# GH_Terra_one_side_corr.net
KiCad netlist of a schematic drawn in EAGLE
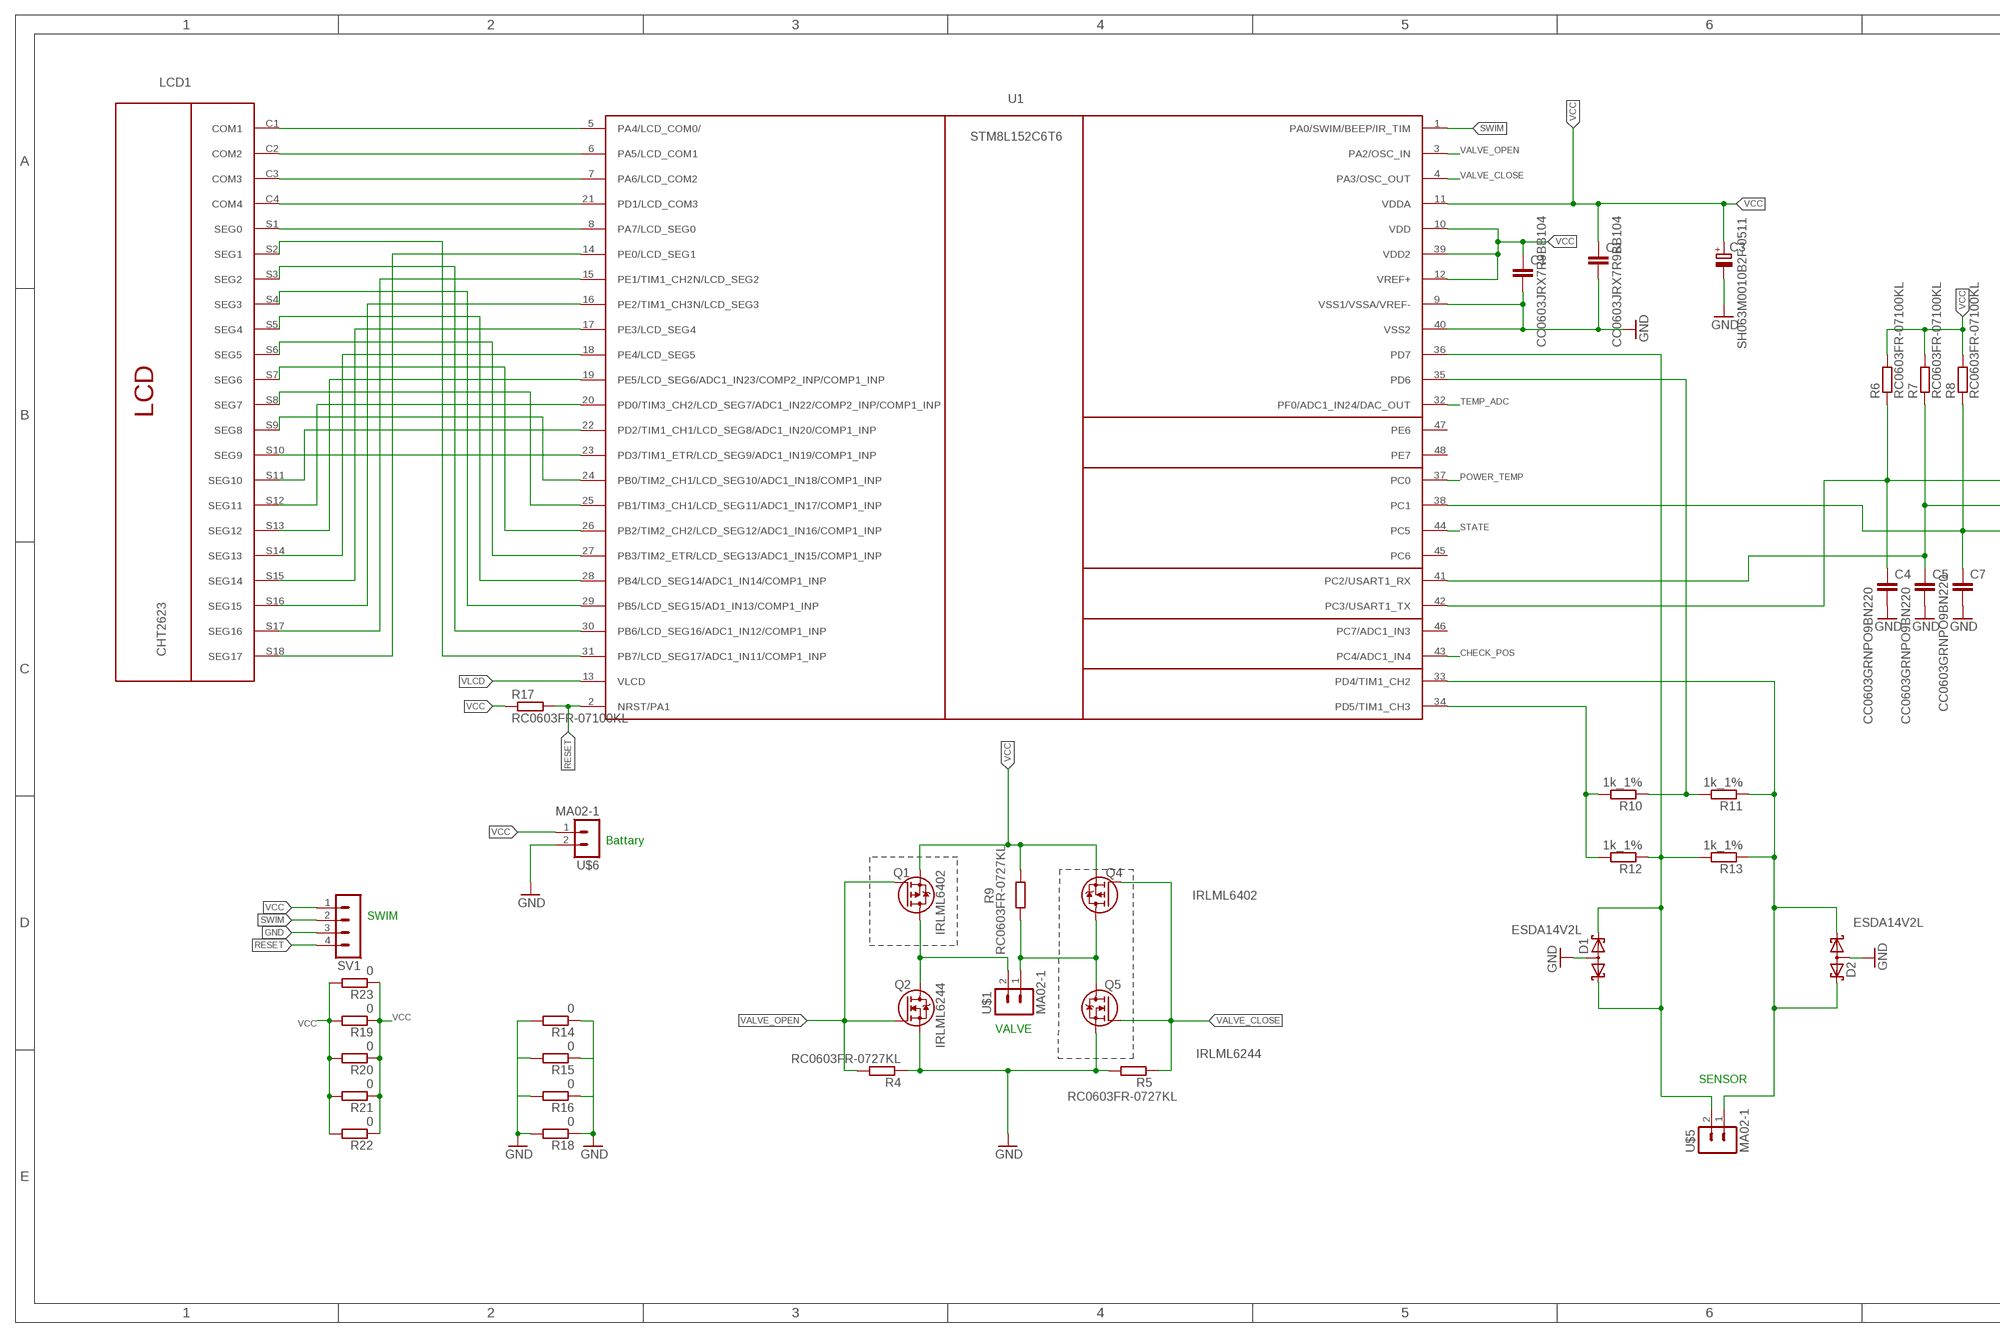
[diagram p0: schematic, sheet 1, part 1 of 2]
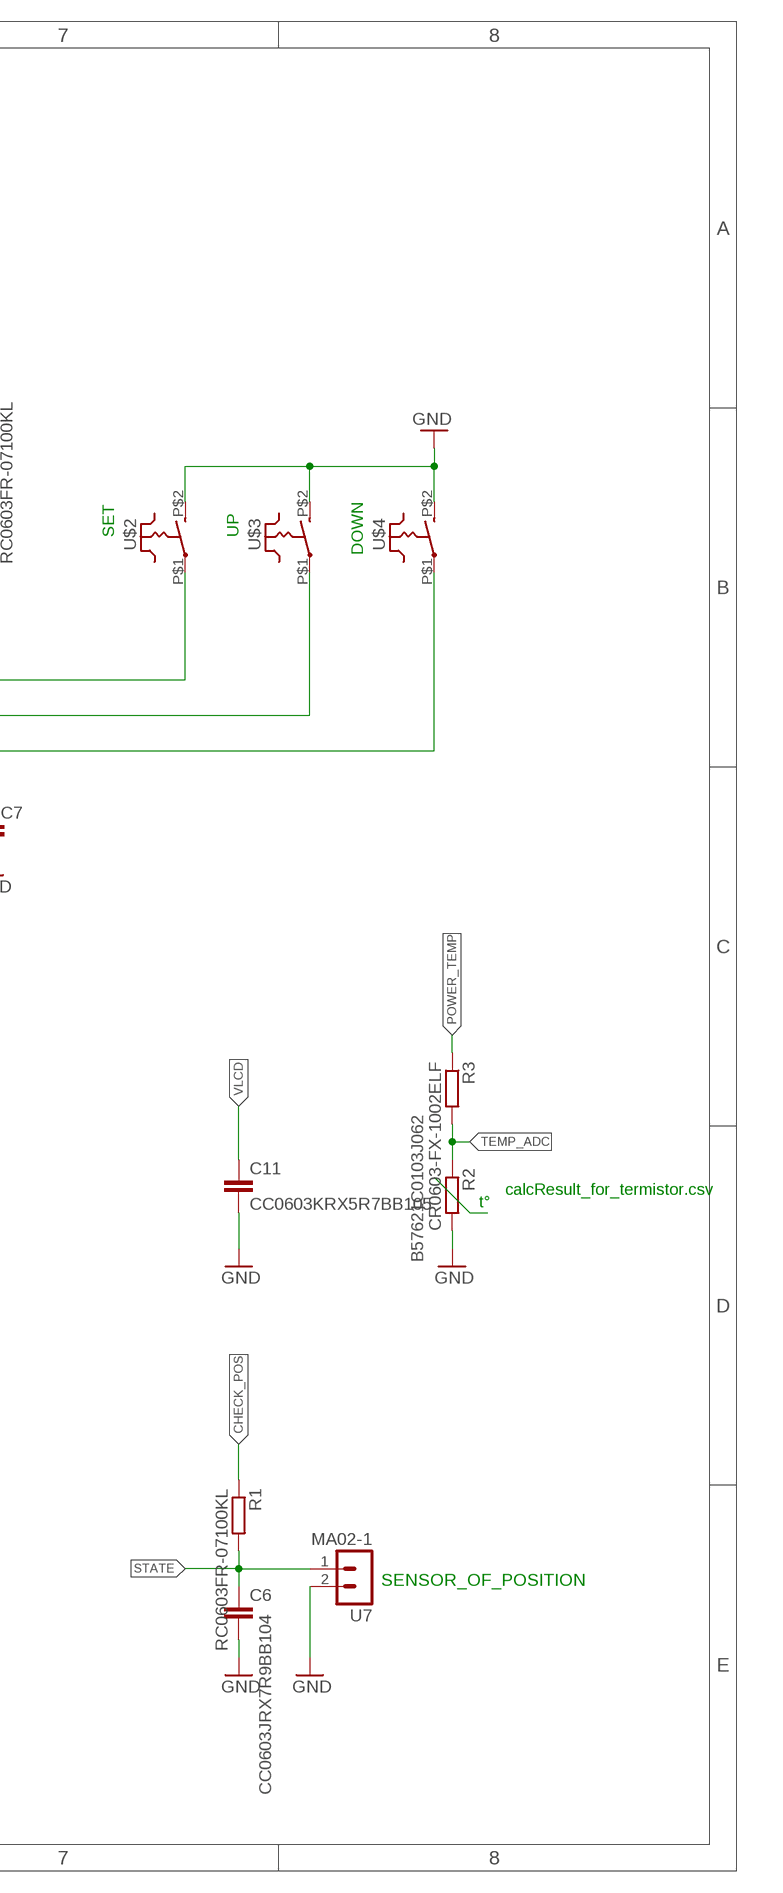
[diagram p1: schematic, sheet 1, part 2 of 2]

(export (version "E")
  (design (tool "Eeschema 10.0.6"))
  (components
    (comp (ref "C1")
      (value "CC0603JRX7R9BB104")
      (footprint "eagle-import:C0603_IPC")
      (libsource (lib "eagle-import") (part "C-EUC0603"))
    )
    (comp (ref "C2")
      (value "CC0603JRX7R9BB104")
      (footprint "eagle-import:C0603_IPC")
      (libsource (lib "eagle-import") (part "C-EUC0603"))
    )
    (comp (ref "C3")
      (value "SH063M0010B2F-0511")
      (footprint "eagle-import:SANYO-OSCON_C6")
      (libsource (lib "eagle-import") (part "CPOL-EUSANYO_C6"))
    )
    (comp (ref "C4")
      (value "CC0603GRNPO9BN220")
      (footprint "eagle-import:C0603_IPC")
      (libsource (lib "eagle-import") (part "C-EUC0603"))
    )
    (comp (ref "C5")
      (value "CC0603GRNPO9BN220")
      (footprint "eagle-import:C0603_IPC")
      (libsource (lib "eagle-import") (part "C-EUC0603"))
    )
    (comp (ref "C6")
      (value "CC0603JRX7R9BB104")
      (footprint "eagle-import:C0603_IPC")
      (libsource (lib "eagle-import") (part "C-EUC0603"))
    )
    (comp (ref "C7")
      (value "CC0603GRNPO9BN220")
      (footprint "eagle-import:C0603_IPC")
      (libsource (lib "eagle-import") (part "C-EUC0603"))
    )
    (comp (ref "C11")
      (value "CC0603KRX5R7BB105")
      (footprint "eagle-import:C0603_IPC")
      (libsource (lib "eagle-import") (part "C-EUC0603"))
    )
    (comp (ref "D1")
      (value "ESDA14V2L")
      (footprint "eagle-import:SOT23")
      (libsource (lib "eagle-import") (part "BAS40-06"))
    )
    (comp (ref "D2")
      (value "ESDA14V2L")
      (footprint "eagle-import:SOT23")
      (libsource (lib "eagle-import") (part "BAS40-06"))
    )
    (comp (ref "LCD1")
      (value "CHT2623")
      (footprint "eagle-import:CHT2623")
      (libsource (lib "eagle-import") (part "CHT2623"))
    )
    (comp (ref "Q1")
      (value "IRLML6402")
      (footprint "eagle-import:SOT23")
      (libsource (lib "eagle-import") (part "PFET-SOT23"))
    )
    (comp (ref "Q2")
      (value "IRLML6244")
      (footprint "eagle-import:SOT23")
      (libsource (lib "eagle-import") (part "NFET-SOT23"))
    )
    (comp (ref "Q4")
      (value "IRLML6402")
      (footprint "eagle-import:SOT23")
      (libsource (lib "eagle-import") (part "PFET-SOT23"))
    )
    (comp (ref "Q5")
      (value "IRLML6244")
      (footprint "eagle-import:SOT23")
      (libsource (lib "eagle-import") (part "NFET-SOT23"))
    )
    (comp (ref "R1")
      (value "RC0603FR-07100KL")
      (footprint "eagle-import:R0603_IPC")
      (libsource (lib "eagle-import") (part "R-EU_R0603"))
    )
    (comp (ref "R2")
      (value "B57621C0103J062")
      (footprint "eagle-import:R1206")
      (libsource (lib "eagle-import") (part "R-EU_R1206"))
    )
    (comp (ref "R3")
      (value "CR0603-FX-1002ELF")
      (footprint "eagle-import:R0603_IPC")
      (libsource (lib "eagle-import") (part "R-EU_R0603"))
    )
    (comp (ref "R4")
      (value "RC0603FR-0727KL")
      (footprint "eagle-import:R0603_IPC")
      (libsource (lib "eagle-import") (part "R-EU_R0603"))
    )
    (comp (ref "R5")
      (value "RC0603FR-0727KL")
      (footprint "eagle-import:R0603_IPC")
      (libsource (lib "eagle-import") (part "R-EU_R0603"))
    )
    (comp (ref "R6")
      (value "RC0603FR-07100KL")
      (footprint "eagle-import:R0603_IPC")
      (libsource (lib "eagle-import") (part "R-EU_R0603"))
    )
    (comp (ref "R7")
      (value "RC0603FR-07100KL")
      (footprint "eagle-import:R0603_IPC")
      (libsource (lib "eagle-import") (part "R-EU_R0603"))
    )
    (comp (ref "R8")
      (value "RC0603FR-07100KL")
      (footprint "eagle-import:R0603_IPC")
      (libsource (lib "eagle-import") (part "R-EU_R0603"))
    )
    (comp (ref "R9")
      (value "RC0603FR-0727KL")
      (footprint "eagle-import:R0603_IPC")
      (libsource (lib "eagle-import") (part "R-EU_R0603"))
    )
    (comp (ref "R10")
      (value "1k_1%")
      (footprint "eagle-import:R0603_IPC")
      (libsource (lib "eagle-import") (part "R-EU_R0603"))
    )
    (comp (ref "R11")
      (value "1k_1%")
      (footprint "eagle-import:R0603_IPC")
      (libsource (lib "eagle-import") (part "R-EU_R0603"))
    )
    (comp (ref "R12")
      (value "1k_1%")
      (footprint "eagle-import:R0603_IPC")
      (libsource (lib "eagle-import") (part "R-EU_R0603"))
    )
    (comp (ref "R13")
      (value "1k_1%")
      (footprint "eagle-import:R0603_IPC")
      (libsource (lib "eagle-import") (part "R-EU_R0603"))
    )
    (comp (ref "R14")
      (value "0")
      (footprint "eagle-import:R0603_IPC")
      (libsource (lib "eagle-import") (part "R-EU_R0603"))
    )
    (comp (ref "R15")
      (value "0")
      (footprint "eagle-import:R0603_IPC")
      (libsource (lib "eagle-import") (part "R-EU_R0603"))
    )
    (comp (ref "R16")
      (value "0")
      (footprint "eagle-import:R0603_IPC")
      (libsource (lib "eagle-import") (part "R-EU_R0603"))
    )
    (comp (ref "R17")
      (value "RC0603FR-07100KL")
      (footprint "eagle-import:R0603_IPC")
      (libsource (lib "eagle-import") (part "R-EU_R0603"))
    )
    (comp (ref "R18")
      (value "0")
      (footprint "eagle-import:R0603_IPC")
      (libsource (lib "eagle-import") (part "R-EU_R0603"))
    )
    (comp (ref "R19")
      (value "0")
      (footprint "eagle-import:R0603_IPC")
      (libsource (lib "eagle-import") (part "R-EU_R0603"))
    )
    (comp (ref "R20")
      (value "0")
      (footprint "eagle-import:R0603_IPC")
      (libsource (lib "eagle-import") (part "R-EU_R0603"))
    )
    (comp (ref "R21")
      (value "0")
      (footprint "eagle-import:R0603_IPC")
      (libsource (lib "eagle-import") (part "R-EU_R0603"))
    )
    (comp (ref "R22")
      (value "0")
      (footprint "eagle-import:R0603_IPC")
      (libsource (lib "eagle-import") (part "R-EU_R0603"))
    )
    (comp (ref "R23")
      (value "0")
      (footprint "eagle-import:R0603_IPC")
      (libsource (lib "eagle-import") (part "R-EU_R0603"))
    )
    (comp (ref "SV1")
      (value "MA04-1")
      (footprint "eagle-import:MA04-1")
      (libsource (lib "eagle-import") (part "MA04-1"))
    )
    (comp (ref "U$1")
      (value "MA02-1")
      (footprint "eagle-import:MA02-1")
      (libsource (lib "eagle-import") (part "MA02-1"))
    )
    (comp (ref "U$2")
      (value "RK_4X3")
      (footprint "eagle-import:RK_3X4")
      (libsource (lib "eagle-import") (part "RK_4X3"))
    )
    (comp (ref "U$3")
      (value "RK_4X3")
      (footprint "eagle-import:RK_3X4")
      (libsource (lib "eagle-import") (part "RK_4X3"))
    )
    (comp (ref "U$4")
      (value "RK_4X3")
      (footprint "eagle-import:RK_3X4")
      (libsource (lib "eagle-import") (part "RK_4X3"))
    )
    (comp (ref "U$5")
      (value "MA02-1")
      (footprint "eagle-import:MA02-1")
      (libsource (lib "eagle-import") (part "MA02-1"))
    )
    (comp (ref "U$6")
      (value "MA02-1")
      (footprint "eagle-import:MA02-1")
      (libsource (lib "eagle-import") (part "MA02-1"))
    )
    (comp (ref "U1")
      (value "STM8L152C6T6")
      (footprint "eagle-import:LQFP48")
      (libsource (lib "eagle-import") (part "STM8L152C6"))
    )
    (comp (ref "U7")
      (value "MA02-1")
      (footprint "eagle-import:MA02-1")
      (libsource (lib "eagle-import") (part "MA02-1"))
    )
  )
  (nets
    (net (code "1") (name "CHECK_POS") (class "Default")
      (node (ref "R1") (pin "1") (pinfunction "1_1") (pintype "passive"))
      (node (ref "U1") (pin "43") (pinfunction "PC4/ADC1_IN4_43") (pintype "bidirectional"))
    )
    (net (code "2") (name "GND") (class "Default")
      (node (ref "C1") (pin "2") (pinfunction "2_2") (pintype "passive"))
      (node (ref "C11") (pin "2") (pinfunction "2_2") (pintype "passive"))
      (node (ref "C2") (pin "2") (pinfunction "2_2") (pintype "passive"))
      (node (ref "C3") (pin "-") (pinfunction "-_-") (pintype "passive"))
      (node (ref "C4") (pin "2") (pinfunction "2_2") (pintype "passive"))
      (node (ref "C5") (pin "2") (pinfunction "2_2") (pintype "passive"))
      (node (ref "C6") (pin "2") (pinfunction "2_2") (pintype "passive"))
      (node (ref "C7") (pin "2") (pinfunction "2_2") (pintype "passive"))
      (node (ref "D1") (pin "3") (pinfunction "AA_3") (pintype "passive"))
      (node (ref "D2") (pin "3") (pinfunction "AA_3") (pintype "passive"))
      (node (ref "Q2") (pin "2") (pinfunction "S_2") (pintype "passive"))
      (node (ref "Q5") (pin "2") (pinfunction "S_2") (pintype "passive"))
      (node (ref "R14") (pin "1") (pinfunction "1_1") (pintype "passive"))
      (node (ref "R14") (pin "2") (pinfunction "2_2") (pintype "passive"))
      (node (ref "R15") (pin "1") (pinfunction "1_1") (pintype "passive"))
      (node (ref "R15") (pin "2") (pinfunction "2_2") (pintype "passive"))
      (node (ref "R16") (pin "1") (pinfunction "1_1") (pintype "passive"))
      (node (ref "R16") (pin "2") (pinfunction "2_2") (pintype "passive"))
      (node (ref "R18") (pin "1") (pinfunction "1_1") (pintype "passive"))
      (node (ref "R18") (pin "2") (pinfunction "2_2") (pintype "passive"))
      (node (ref "R2") (pin "2") (pinfunction "2_2") (pintype "passive"))
      (node (ref "R4") (pin "1") (pinfunction "1_1") (pintype "passive"))
      (node (ref "R5") (pin "2") (pinfunction "2_2") (pintype "passive"))
      (node (ref "SV1") (pin "3") (pinfunction "3_3") (pintype "passive"))
      (node (ref "U$2") (pin "P$2") (pinfunction "S_P$2") (pintype "passive"))
      (node (ref "U$3") (pin "P$2") (pinfunction "S_P$2") (pintype "passive"))
      (node (ref "U$4") (pin "P$2") (pinfunction "S_P$2") (pintype "passive"))
      (node (ref "U$6") (pin "2") (pinfunction "2_2") (pintype "passive"))
      (node (ref "U1") (pin "40") (pinfunction "VSS2_40") (pintype "bidirectional"))
      (node (ref "U1") (pin "9") (pinfunction "VSS1/VSSA/VREF-_9") (pintype "bidirectional"))
      (node (ref "U7") (pin "2") (pinfunction "2_2") (pintype "passive"))
    )
    (net (code "3") (name "Net-(D1-K1)") (class "Default")
      (node (ref "D1") (pin "1") (pinfunction "K1_1") (pintype "passive"))
      (node (ref "D1") (pin "2") (pinfunction "K2_2") (pintype "passive"))
      (node (ref "R12") (pin "1") (pinfunction "1_1") (pintype "passive"))
      (node (ref "R13") (pin "2") (pinfunction "2_2") (pintype "passive"))
      (node (ref "U$5") (pin "2") (pinfunction "2_2") (pintype "passive"))
      (node (ref "U1") (pin "36") (pinfunction "PD7_36") (pintype "bidirectional"))
    )
    (net (code "4") (name "Net-(D2-K1)") (class "Default")
      (node (ref "D2") (pin "1") (pinfunction "K1_1") (pintype "passive"))
      (node (ref "D2") (pin "2") (pinfunction "K2_2") (pintype "passive"))
      (node (ref "R11") (pin "1") (pinfunction "1_1") (pintype "passive"))
      (node (ref "R13") (pin "1") (pinfunction "1_1") (pintype "passive"))
      (node (ref "U$5") (pin "1") (pinfunction "1_1") (pintype "passive"))
      (node (ref "U1") (pin "33") (pinfunction "PD4/TIM1_CH2_33") (pintype "bidirectional"))
    )
    (net (code "5") (name "Net-(LCD1-COM1)") (class "Default")
      (node (ref "LCD1") (pin "C1") (pinfunction "COM1_C1") (pintype "bidirectional"))
      (node (ref "U1") (pin "5") (pinfunction "PA4/LCD_COM0/_5") (pintype "bidirectional"))
    )
    (net (code "6") (name "Net-(LCD1-COM2)") (class "Default")
      (node (ref "LCD1") (pin "C2") (pinfunction "COM2_C2") (pintype "bidirectional"))
      (node (ref "U1") (pin "6") (pinfunction "PA5/LCD_COM1_6") (pintype "bidirectional"))
    )
    (net (code "7") (name "Net-(LCD1-COM3)") (class "Default")
      (node (ref "LCD1") (pin "C3") (pinfunction "COM3_C3") (pintype "bidirectional"))
      (node (ref "U1") (pin "7") (pinfunction "PA6/LCD_COM2_7") (pintype "bidirectional"))
    )
    (net (code "8") (name "Net-(LCD1-COM4)") (class "Default")
      (node (ref "LCD1") (pin "C4") (pinfunction "COM4_C4") (pintype "bidirectional"))
      (node (ref "U1") (pin "21") (pinfunction "PD1/LCD_COM3_21") (pintype "bidirectional"))
    )
    (net (code "9") (name "Net-(LCD1-SEG0)") (class "Default")
      (node (ref "LCD1") (pin "S1") (pinfunction "SEG0_S1") (pintype "bidirectional"))
      (node (ref "U1") (pin "8") (pinfunction "PA7/LCD_SEG0_8") (pintype "bidirectional"))
    )
    (net (code "10") (name "Net-(LCD1-SEG1)") (class "Default")
      (node (ref "LCD1") (pin "S2") (pinfunction "SEG1_S2") (pintype "bidirectional"))
      (node (ref "U1") (pin "31") (pinfunction "PB7/LCD_SEG17/ADC1_IN11/COMP1_INP_31") (pintype "bidirectional"))
    )
    (net (code "11") (name "Net-(LCD1-SEG2)") (class "Default")
      (node (ref "LCD1") (pin "S3") (pinfunction "SEG2_S3") (pintype "bidirectional"))
      (node (ref "U1") (pin "30") (pinfunction "PB6/LCD_SEG16/ADC1_IN12/COMP1_INP_30") (pintype "bidirectional"))
    )
    (net (code "12") (name "Net-(LCD1-SEG3)") (class "Default")
      (node (ref "LCD1") (pin "S4") (pinfunction "SEG3_S4") (pintype "bidirectional"))
      (node (ref "U1") (pin "29") (pinfunction "PB5/LCD_SEG15/AD1_IN13/COMP1_INP_29") (pintype "bidirectional"))
    )
    (net (code "13") (name "Net-(LCD1-SEG4)") (class "Default")
      (node (ref "LCD1") (pin "S5") (pinfunction "SEG4_S5") (pintype "bidirectional"))
      (node (ref "U1") (pin "28") (pinfunction "PB4/LCD_SEG14/ADC1_IN14/COMP1_INP_28") (pintype "bidirectional"))
    )
    (net (code "14") (name "Net-(LCD1-SEG5)") (class "Default")
      (node (ref "LCD1") (pin "S6") (pinfunction "SEG5_S6") (pintype "bidirectional"))
      (node (ref "U1") (pin "27") (pinfunction "PB3/TIM2_ETR/LCD_SEG13/ADC1_IN15/COMP1_INP_27") (pintype "bidirectional"))
    )
    (net (code "15") (name "Net-(LCD1-SEG6)") (class "Default")
      (node (ref "LCD1") (pin "S7") (pinfunction "SEG6_S7") (pintype "bidirectional"))
      (node (ref "U1") (pin "26") (pinfunction "PB2/TIM2_CH2/LCD_SEG12/ADC1_IN16/COMP1_INP_26") (pintype "bidirectional"))
    )
    (net (code "16") (name "Net-(LCD1-SEG7)") (class "Default")
      (node (ref "LCD1") (pin "S8") (pinfunction "SEG7_S8") (pintype "bidirectional"))
      (node (ref "U1") (pin "25") (pinfunction "PB1/TIM3_CH1/LCD_SEG11/ADC1_IN17/COMP1_INP_25") (pintype "bidirectional"))
    )
    (net (code "17") (name "Net-(LCD1-SEG8)") (class "Default")
      (node (ref "LCD1") (pin "S9") (pinfunction "SEG8_S9") (pintype "bidirectional"))
      (node (ref "U1") (pin "24") (pinfunction "PB0/TIM2_CH1/LCD_SEG10/ADC1_IN18/COMP1_INP_24") (pintype "bidirectional"))
    )
    (net (code "18") (name "Net-(LCD1-SEG9)") (class "Default")
      (node (ref "LCD1") (pin "S10") (pinfunction "SEG9_S10") (pintype "bidirectional"))
      (node (ref "U1") (pin "23") (pinfunction "PD3/TIM1_ETR/LCD_SEG9/ADC1_IN19/COMP1_INP_23") (pintype "bidirectional"))
    )
    (net (code "19") (name "Net-(LCD1-SEG10)") (class "Default")
      (node (ref "LCD1") (pin "S11") (pinfunction "SEG10_S11") (pintype "bidirectional"))
      (node (ref "U1") (pin "22") (pinfunction "PD2/TIM1_CH1/LCD_SEG8/ADC1_IN20/COMP1_INP_22") (pintype "bidirectional"))
    )
    (net (code "20") (name "Net-(LCD1-SEG11)") (class "Default")
      (node (ref "LCD1") (pin "S12") (pinfunction "SEG11_S12") (pintype "bidirectional"))
      (node (ref "U1") (pin "20") (pinfunction "PD0/TIM3_CH2/LCD_SEG7/ADC1_IN22/COMP2_INP/COMP1_INP_20") (pintype "bidirectional"))
    )
    (net (code "21") (name "Net-(LCD1-SEG12)") (class "Default")
      (node (ref "LCD1") (pin "S13") (pinfunction "SEG12_S13") (pintype "bidirectional"))
      (node (ref "U1") (pin "19") (pinfunction "PE5/LCD_SEG6/ADC1_IN23/COMP2_INP/COMP1_INP_19") (pintype "bidirectional"))
    )
    (net (code "22") (name "Net-(LCD1-SEG13)") (class "Default")
      (node (ref "LCD1") (pin "S14") (pinfunction "SEG13_S14") (pintype "bidirectional"))
      (node (ref "U1") (pin "18") (pinfunction "PE4/LCD_SEG5_18") (pintype "bidirectional"))
    )
    (net (code "23") (name "Net-(LCD1-SEG14)") (class "Default")
      (node (ref "LCD1") (pin "S15") (pinfunction "SEG14_S15") (pintype "bidirectional"))
      (node (ref "U1") (pin "17") (pinfunction "PE3/LCD_SEG4_17") (pintype "bidirectional"))
    )
    (net (code "24") (name "Net-(LCD1-SEG15)") (class "Default")
      (node (ref "LCD1") (pin "S16") (pinfunction "SEG15_S16") (pintype "bidirectional"))
      (node (ref "U1") (pin "16") (pinfunction "PE2/TIM1_CH3N/LCD_SEG3_16") (pintype "bidirectional"))
    )
    (net (code "25") (name "Net-(LCD1-SEG16)") (class "Default")
      (node (ref "LCD1") (pin "S17") (pinfunction "SEG16_S17") (pintype "bidirectional"))
      (node (ref "U1") (pin "15") (pinfunction "PE1/TIM1_CH2N/LCD_SEG2_15") (pintype "bidirectional"))
    )
    (net (code "26") (name "Net-(LCD1-SEG17)") (class "Default")
      (node (ref "LCD1") (pin "S18") (pinfunction "SEG17_S18") (pintype "bidirectional"))
      (node (ref "U1") (pin "14") (pinfunction "PE0/LCD_SEG1_14") (pintype "bidirectional"))
    )
    (net (code "27") (name "Net-(Q1-D)") (class "Default")
      (node (ref "Q1") (pin "3") (pinfunction "D_3") (pintype "passive"))
      (node (ref "Q2") (pin "3") (pinfunction "D_3") (pintype "passive"))
      (node (ref "U$1") (pin "2") (pinfunction "2_2") (pintype "passive"))
    )
    (net (code "28") (name "Net-(Q4-D)") (class "Default")
      (node (ref "Q4") (pin "3") (pinfunction "D_3") (pintype "passive"))
      (node (ref "Q5") (pin "3") (pinfunction "D_3") (pintype "passive"))
      (node (ref "R9") (pin "2") (pinfunction "2_2") (pintype "passive"))
      (node (ref "U$1") (pin "1") (pinfunction "1_1") (pintype "passive"))
    )
    (net (code "29") (name "Net-(U$2-P)") (class "Default")
      (node (ref "C4") (pin "1") (pinfunction "1_1") (pintype "passive"))
      (node (ref "R6") (pin "1") (pinfunction "1_1") (pintype "passive"))
      (node (ref "U$2") (pin "P$1") (pinfunction "P_P$1") (pintype "passive"))
      (node (ref "U1") (pin "42") (pinfunction "PC3/USART1_TX_42") (pintype "bidirectional"))
    )
    (net (code "30") (name "Net-(U$3-P)") (class "Default")
      (node (ref "C5") (pin "1") (pinfunction "1_1") (pintype "passive"))
      (node (ref "R7") (pin "1") (pinfunction "1_1") (pintype "passive"))
      (node (ref "U$3") (pin "P$1") (pinfunction "P_P$1") (pintype "passive"))
      (node (ref "U1") (pin "41") (pinfunction "PC2/USART1_RX_41") (pintype "bidirectional"))
    )
    (net (code "31") (name "Net-(U$4-P)") (class "Default")
      (node (ref "C7") (pin "1") (pinfunction "1_1") (pintype "passive"))
      (node (ref "R8") (pin "1") (pinfunction "1_1") (pintype "passive"))
      (node (ref "U$4") (pin "P$1") (pinfunction "P_P$1") (pintype "passive"))
      (node (ref "U1") (pin "38") (pinfunction "PC1_38") (pintype "bidirectional"))
    )
    (net (code "32") (name "Net-(U1-PD5{slash}TIM1_CH3)") (class "Default")
      (node (ref "R10") (pin "2") (pinfunction "2_2") (pintype "passive"))
      (node (ref "R12") (pin "2") (pinfunction "2_2") (pintype "passive"))
      (node (ref "U1") (pin "34") (pinfunction "PD5/TIM1_CH3_34") (pintype "bidirectional"))
    )
    (net (code "33") (name "Net-(U1-PD6)") (class "Default")
      (node (ref "R10") (pin "1") (pinfunction "1_1") (pintype "passive"))
      (node (ref "R11") (pin "2") (pinfunction "2_2") (pintype "passive"))
      (node (ref "U1") (pin "35") (pinfunction "PD6_35") (pintype "bidirectional"))
    )
    (net (code "34") (name "POWER_TEMP") (class "Default")
      (node (ref "R3") (pin "1") (pinfunction "1_1") (pintype "passive"))
      (node (ref "U1") (pin "37") (pinfunction "PC0_37") (pintype "bidirectional"))
    )
    (net (code "35") (name "RESET") (class "Default")
      (node (ref "R17") (pin "2") (pinfunction "2_2") (pintype "passive"))
      (node (ref "SV1") (pin "4") (pinfunction "4_4") (pintype "passive"))
      (node (ref "U1") (pin "2") (pinfunction "NRST/PA1_2") (pintype "bidirectional"))
    )
    (net (code "36") (name "STATE") (class "Default")
      (node (ref "C6") (pin "1") (pinfunction "1_1") (pintype "passive"))
      (node (ref "R1") (pin "2") (pinfunction "2_2") (pintype "passive"))
      (node (ref "U1") (pin "44") (pinfunction "PC5_44") (pintype "bidirectional"))
      (node (ref "U7") (pin "1") (pinfunction "1_1") (pintype "passive"))
    )
    (net (code "37") (name "SWIM") (class "Default")
      (node (ref "SV1") (pin "2") (pinfunction "2_2") (pintype "passive"))
      (node (ref "U1") (pin "1") (pinfunction "PA0/SWIM/BEEP/IR_TIM_1") (pintype "bidirectional"))
    )
    (net (code "38") (name "TEMP_ADC") (class "Default")
      (node (ref "R2") (pin "1") (pinfunction "1_1") (pintype "passive"))
      (node (ref "R3") (pin "2") (pinfunction "2_2") (pintype "passive"))
      (node (ref "U1") (pin "32") (pinfunction "PF0/ADC1_IN24/DAC_OUT_32") (pintype "bidirectional"))
    )
    (net (code "39") (name "VALVE_CLOSE") (class "Default")
      (node (ref "Q4") (pin "1") (pinfunction "G_1") (pintype "passive"))
      (node (ref "Q5") (pin "1") (pinfunction "G_1") (pintype "passive"))
      (node (ref "R5") (pin "1") (pinfunction "1_1") (pintype "passive"))
      (node (ref "U1") (pin "4") (pinfunction "PA3/OSC_OUT_4") (pintype "bidirectional"))
    )
    (net (code "40") (name "VALVE_OPEN") (class "Default")
      (node (ref "Q1") (pin "1") (pinfunction "G_1") (pintype "passive"))
      (node (ref "Q2") (pin "1") (pinfunction "G_1") (pintype "passive"))
      (node (ref "R4") (pin "2") (pinfunction "2_2") (pintype "passive"))
      (node (ref "U1") (pin "3") (pinfunction "PA2/OSC_IN_3") (pintype "bidirectional"))
    )
    (net (code "41") (name "VCC") (class "Default")
      (node (ref "C1") (pin "1") (pinfunction "1_1") (pintype "passive"))
      (node (ref "C2") (pin "1") (pinfunction "1_1") (pintype "passive"))
      (node (ref "C3") (pin "+") (pinfunction "+_+") (pintype "passive"))
      (node (ref "Q1") (pin "2") (pinfunction "S_2") (pintype "passive"))
      (node (ref "Q4") (pin "2") (pinfunction "S_2") (pintype "passive"))
      (node (ref "R17") (pin "1") (pinfunction "1_1") (pintype "passive"))
      (node (ref "R19") (pin "1") (pinfunction "1_1") (pintype "passive"))
      (node (ref "R19") (pin "2") (pinfunction "2_2") (pintype "passive"))
      (node (ref "R20") (pin "1") (pinfunction "1_1") (pintype "passive"))
      (node (ref "R20") (pin "2") (pinfunction "2_2") (pintype "passive"))
      (node (ref "R21") (pin "1") (pinfunction "1_1") (pintype "passive"))
      (node (ref "R21") (pin "2") (pinfunction "2_2") (pintype "passive"))
      (node (ref "R22") (pin "1") (pinfunction "1_1") (pintype "passive"))
      (node (ref "R22") (pin "2") (pinfunction "2_2") (pintype "passive"))
      (node (ref "R23") (pin "1") (pinfunction "1_1") (pintype "passive"))
      (node (ref "R23") (pin "2") (pinfunction "2_2") (pintype "passive"))
      (node (ref "R6") (pin "2") (pinfunction "2_2") (pintype "passive"))
      (node (ref "R7") (pin "2") (pinfunction "2_2") (pintype "passive"))
      (node (ref "R8") (pin "2") (pinfunction "2_2") (pintype "passive"))
      (node (ref "R9") (pin "1") (pinfunction "1_1") (pintype "passive"))
      (node (ref "SV1") (pin "1") (pinfunction "1_1") (pintype "passive"))
      (node (ref "U$6") (pin "1") (pinfunction "1_1") (pintype "passive"))
      (node (ref "U1") (pin "10") (pinfunction "VDD_10") (pintype "bidirectional"))
      (node (ref "U1") (pin "11") (pinfunction "VDDA_11") (pintype "bidirectional"))
      (node (ref "U1") (pin "12") (pinfunction "VREF+_12") (pintype "bidirectional"))
      (node (ref "U1") (pin "39") (pinfunction "VDD2_39") (pintype "bidirectional"))
    )
    (net (code "42") (name "VLCD") (class "Default")
      (node (ref "C11") (pin "1") (pinfunction "1_1") (pintype "passive"))
      (node (ref "U1") (pin "13") (pinfunction "VLCD_13") (pintype "bidirectional"))
    )
    (net (code "43") (name "unconnected-(U1-PC6-Pad45)") (class "Default")
      (node (ref "U1") (pin "45") (pinfunction "PC6_45") (pintype "bidirectional"))
    )
    (net (code "44") (name "unconnected-(U1-PC7{slash}ADC1_IN3-Pad46)") (class "Default")
      (node (ref "U1") (pin "46") (pinfunction "PC7/ADC1_IN3_46") (pintype "bidirectional"))
    )
    (net (code "45") (name "unconnected-(U1-PE6-Pad47)") (class "Default")
      (node (ref "U1") (pin "47") (pinfunction "PE6_47") (pintype "bidirectional"))
    )
    (net (code "46") (name "unconnected-(U1-PE7-Pad48)") (class "Default")
      (node (ref "U1") (pin "48") (pinfunction "PE7_48") (pintype "bidirectional"))
    )
  )
)
